# MPPT.net
KiCad netlist of a schematic drawn in Altium Designer
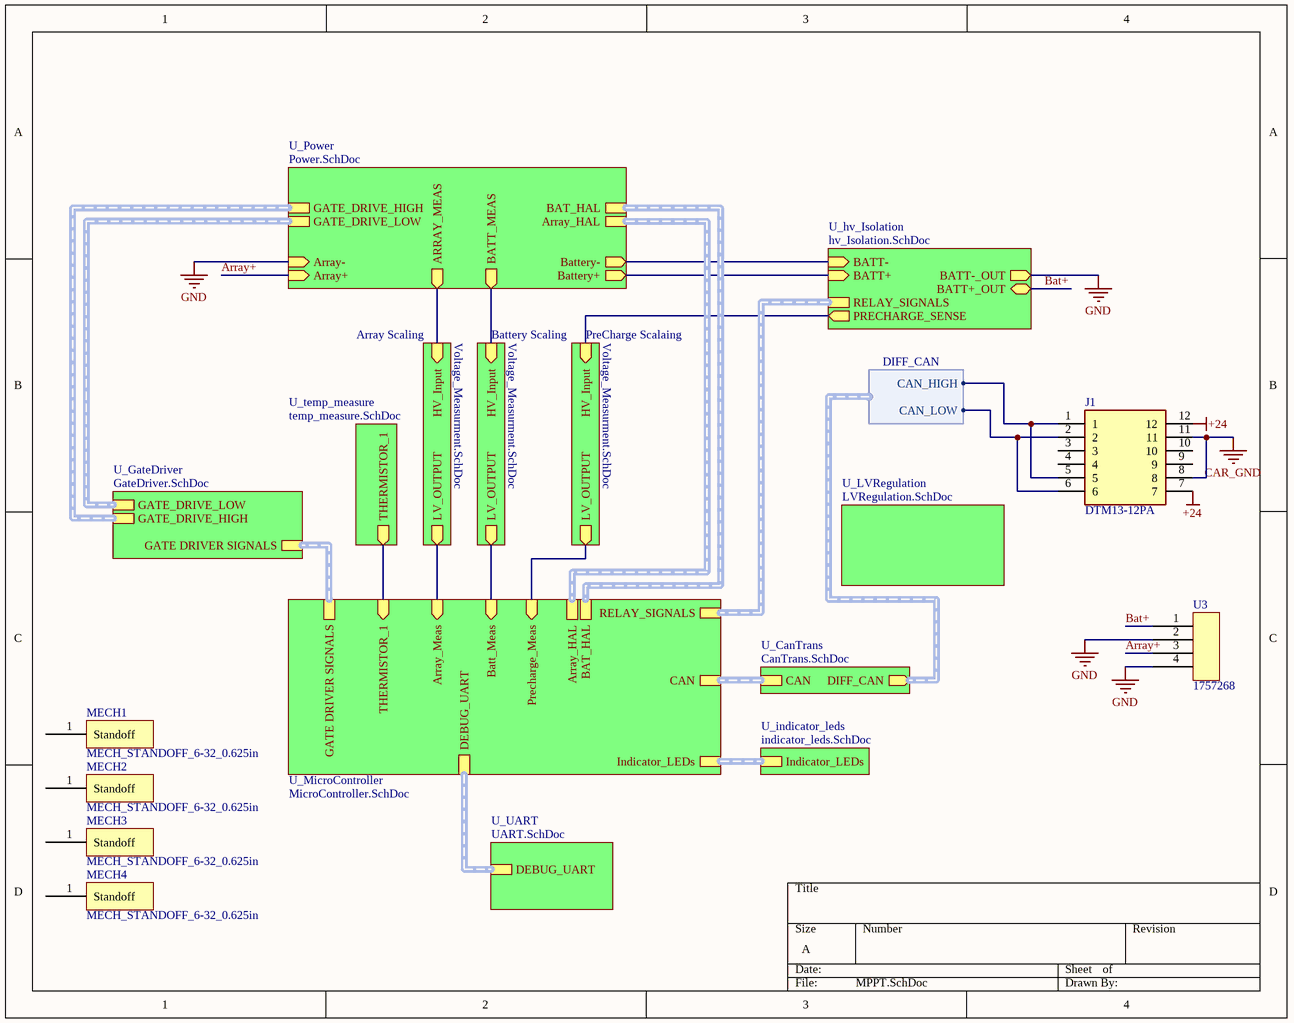
[diagram p0: MPPT.SchDoc]

(export (version "E")
  (design (tool "Eeschema 10.0.6"))
  (components
    (comp (ref "J1")
      (value "DTM13-12PA")
      (footprint "TE_DTM13-12PA")
      (libsource (lib "University of Minnesota - Solar Vehicle Project") (part "DTM13-12PA"))
    )
    (comp (ref "MECH1")
      (value "MECH_STANDOFF_6-32_0.625in")
      (footprint "STANDOFF_6-32_0.625in")
      (description "Hex Standoff Threaded #6-32 Aluminum 0.625\" (15.88mm) 5/8\"")
      (libsource (lib "University of Minnesota - Solar Vehicle Project") (part "Symbol"))
    )
    (comp (ref "MECH2")
      (value "MECH_STANDOFF_6-32_0.625in")
      (footprint "STANDOFF_6-32_0.625in")
      (description "Hex Standoff Threaded #6-32 Aluminum 0.625\" (15.88mm) 5/8\"")
      (libsource (lib "University of Minnesota - Solar Vehicle Project") (part "Symbol"))
    )
    (comp (ref "MECH3")
      (value "MECH_STANDOFF_6-32_0.625in")
      (footprint "STANDOFF_6-32_0.625in")
      (description "Hex Standoff Threaded #6-32 Aluminum 0.625\" (15.88mm) 5/8\"")
      (libsource (lib "University of Minnesota - Solar Vehicle Project") (part "Symbol"))
    )
    (comp (ref "MECH4")
      (value "MECH_STANDOFF_6-32_0.625in")
      (footprint "STANDOFF_6-32_0.625in")
      (description "Hex Standoff Threaded #6-32 Aluminum 0.625\" (15.88mm) 5/8\"")
      (libsource (lib "University of Minnesota - Solar Vehicle Project") (part "Symbol"))
    )
    (comp (ref "U3")
      (value "1757268")
      (footprint "1757268-Footprint-1")
      (description "Strip Terminal Block, 12A, 1 Row(s), 1 Deck(s)")
      (libsource (lib "University of Minnesota - Solar Vehicle Project") (part "1757268-Symbol-1"))
    )
  )
  (nets
    (net (code "2") (name "+24") (class "Default")
      (node (ref "J1") (pin "12") (pinfunction "12_12") (pintype "passive"))
      (node (ref "J1") (pin "7") (pinfunction "7_7") (pintype "passive"))
    )
    (net (code "4") (name "/Array+") (class "Default") (node (ref "U3") (pin "3") (pintype "passive")))
    (net (code "8") (name "/Bat+") (class "Default") (node (ref "U3") (pin "1") (pintype "passive")))
    (net (code "24") (name "CAR_GND") (class "Default")
      (node (ref "J1") (pin "11") (pinfunction "11_11") (pintype "passive"))
      (node (ref "J1") (pin "8") (pinfunction "8_8") (pintype "passive"))
    )
    (net (code "25") (name "GND") (class "Default")
      (node (ref "U3") (pin "2") (pintype "passive"))
      (node (ref "U3") (pin "4") (pintype "passive"))
    )
    (net (code "26") (name "Net-(J1-Pad1)") (class "Default")
      (node (ref "J1") (pin "1") (pinfunction "1_1") (pintype "passive"))
      (node (ref "J1") (pin "5") (pinfunction "5_5") (pintype "passive"))
    )
    (net (code "27") (name "Net-(J1-Pad2)") (class "Default")
      (node (ref "J1") (pin "2") (pinfunction "2_2") (pintype "passive"))
      (node (ref "J1") (pin "6") (pinfunction "6_6") (pintype "passive"))
    )
    (net (code "28") (name "unconnected-(J1-Pad3)") (class "Default")
      (node (ref "J1") (pin "3") (pinfunction "3_3") (pintype "passive"))
    )
    (net (code "29") (name "unconnected-(J1-Pad4)") (class "Default")
      (node (ref "J1") (pin "4") (pinfunction "4_4") (pintype "passive"))
    )
    (net (code "30") (name "unconnected-(J1-Pad9)") (class "Default")
      (node (ref "J1") (pin "9") (pinfunction "9_9") (pintype "passive"))
    )
    (net (code "31") (name "unconnected-(J1-Pad10)") (class "Default")
      (node (ref "J1") (pin "10") (pinfunction "10_10") (pintype "passive"))
    )
    (net (code "32") (name "unconnected-(MECH1-Standoff-Pad1)") (class "Default")
      (node (ref "MECH1") (pin "1") (pinfunction "Standoff_1") (pintype "passive"))
    )
    (net (code "33") (name "unconnected-(MECH2-Standoff-Pad1)") (class "Default")
      (node (ref "MECH2") (pin "1") (pinfunction "Standoff_1") (pintype "passive"))
    )
    (net (code "34") (name "unconnected-(MECH3-Standoff-Pad1)") (class "Default")
      (node (ref "MECH3") (pin "1") (pinfunction "Standoff_1") (pintype "passive"))
    )
    (net (code "35") (name "unconnected-(MECH4-Standoff-Pad1)") (class "Default")
      (node (ref "MECH4") (pin "1") (pinfunction "Standoff_1") (pintype "passive"))
    )
  )
)
